# sound-detector.net
KiCad netlist of a schematic drawn in EAGLE
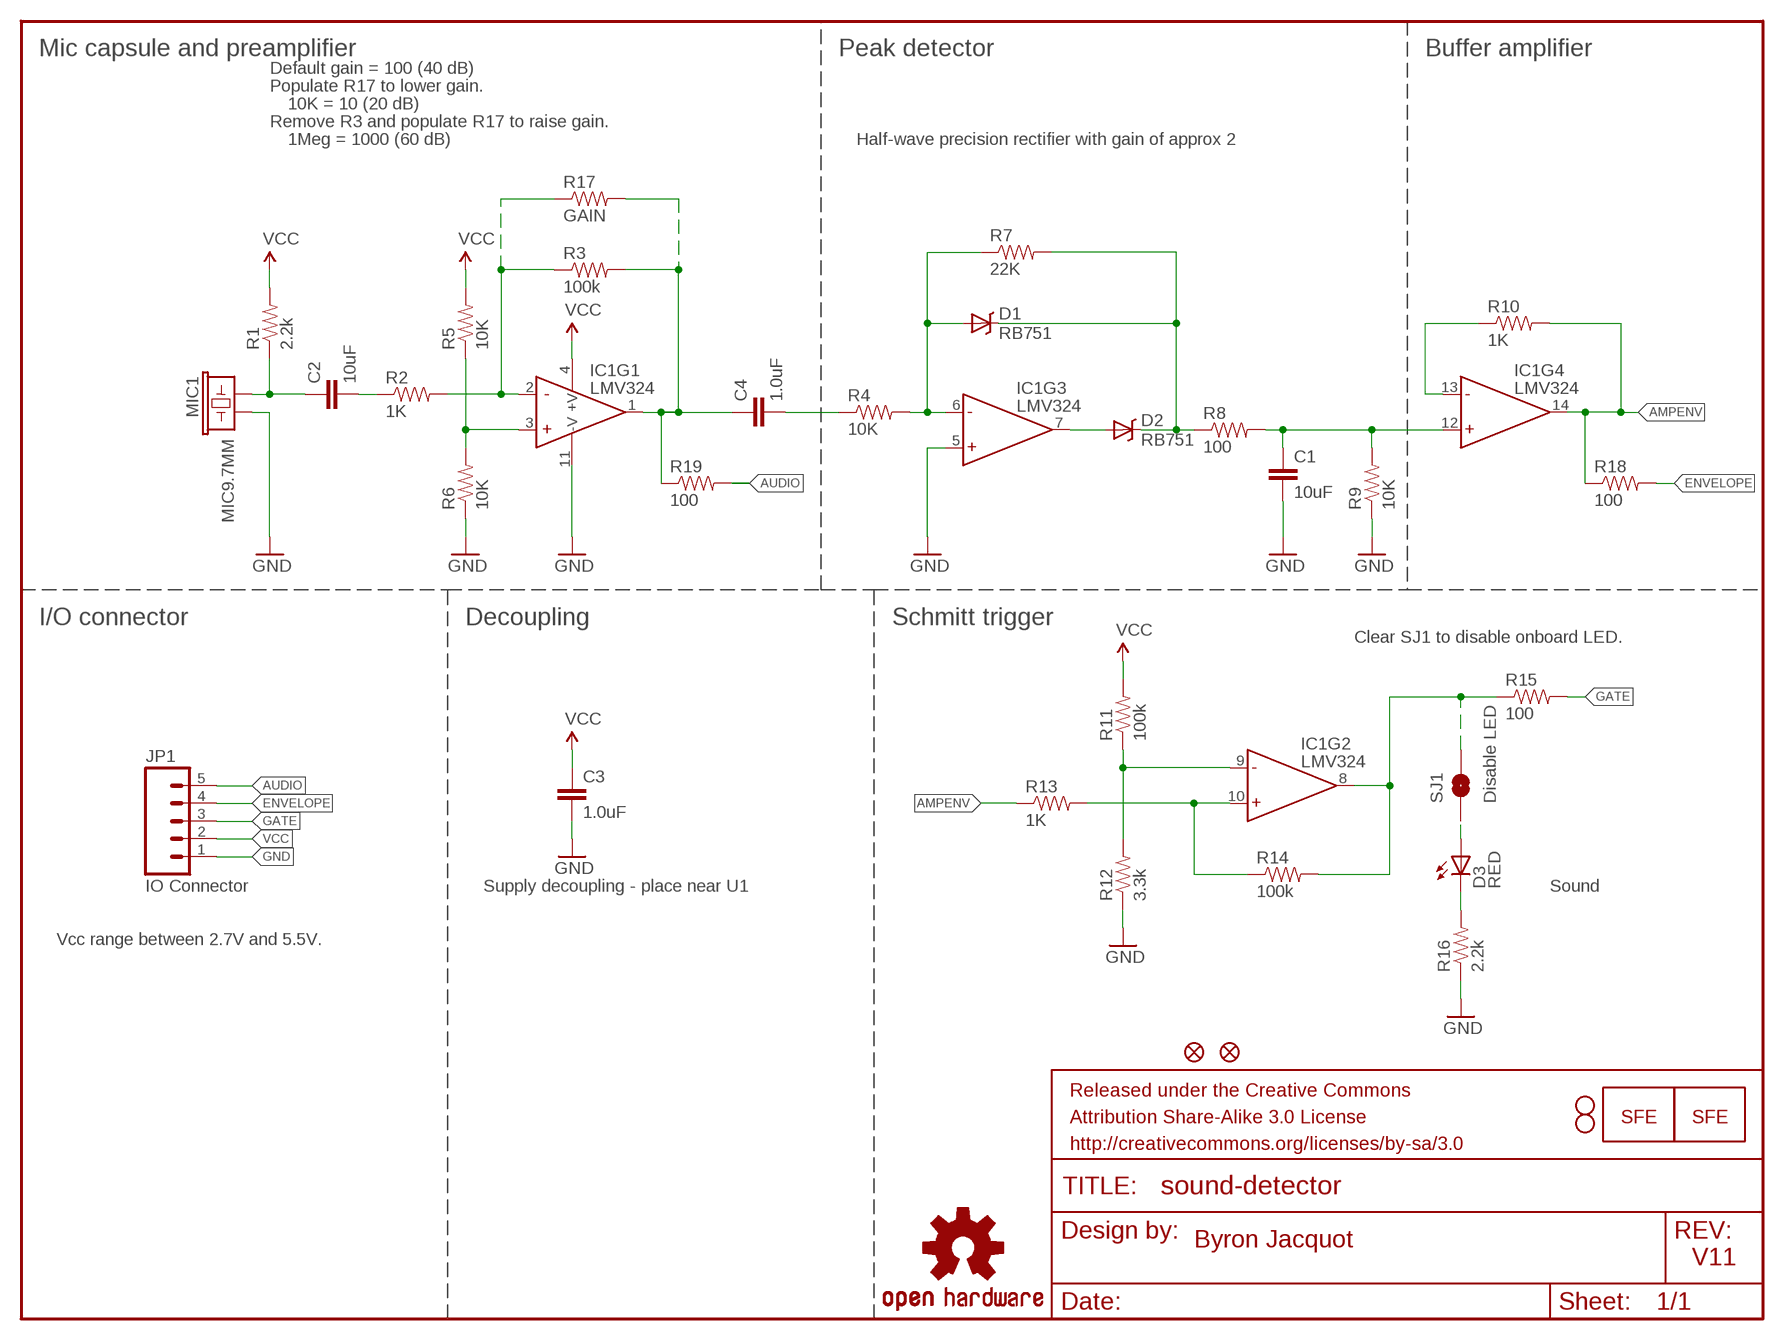
[diagram p0: schematic, sheet 1]

(export (version "E")
  (design (tool "Eeschema 10.0.6"))
  (components
    (comp (ref "C1")
      (value "10uF")
      (footprint "eagle-import:1206")
      (libsource (lib "eagle-import") (part "10UF-6.3V-20%(1206)"))
    )
    (comp (ref "C2")
      (value "10uF")
      (footprint "eagle-import:1206")
      (libsource (lib "eagle-import") (part "10UF-6.3V-20%(1206)"))
    )
    (comp (ref "C3")
      (value "1.0uF")
      (footprint "eagle-import:0603-CAP")
      (libsource (lib "eagle-import") (part "1.0UF-16V-10%(0603)"))
    )
    (comp (ref "C4")
      (value "1.0uF")
      (footprint "eagle-import:0603-CAP")
      (libsource (lib "eagle-import") (part "1.0UF-16V-10%(0603)"))
    )
    (comp (ref "D1")
      (value "RB751")
      (footprint "eagle-import:SOD-523")
      (libsource (lib "eagle-import") (part "RB751"))
    )
    (comp (ref "D2")
      (value "RB751")
      (footprint "eagle-import:SOD-523")
      (libsource (lib "eagle-import") (part "RB751"))
    )
    (comp (ref "D3")
      (value "RED")
      (footprint "eagle-import:LED-0603")
      (libsource (lib "eagle-import") (part "LED-RED0603"))
    )
    (comp (ref "FID3")
      (value "FIDUCIAL1X2")
      (footprint "eagle-import:FIDUCIAL-1X2")
      (libsource (lib "eagle-import") (part "FIDUCIAL1X2"))
    )
    (comp (ref "FID4")
      (value "FIDUCIAL1X2")
      (footprint "eagle-import:FIDUCIAL-1X2")
      (libsource (lib "eagle-import") (part "FIDUCIAL1X2"))
    )
    (comp (ref "FRAME1")
      (value "FRAME-LETTER")
      (footprint "eagle-import:CREATIVE_COMMONS")
      (libsource (lib "eagle-import") (part "FRAME-LETTER"))
    )
    (comp (ref "IC1")
      (value "LMV324")
      (footprint "eagle-import:SO014")
      (libsource (lib "eagle-import") (part "LMV324"))
    )
    (comp (ref "JP1")
      (value "IO Connector")
      (footprint "eagle-import:1X05")
      (libsource (lib "eagle-import") (part "M05PTH"))
    )
    (comp (ref "LOGO1")
      (value "OSHW-LOGOM")
      (footprint "eagle-import:OSHW-LOGO-M")
      (libsource (lib "eagle-import") (part "OSHW-LOGOM"))
    )
    (comp (ref "LOGO2")
      (value "LOGO-SFENW2")
      (footprint "eagle-import:SFE-NEW-WEB")
      (libsource (lib "eagle-import") (part "LOGO-SFENW2"))
    )
    (comp (ref "LOGO3")
      (value "LOGO-SFESK")
      (footprint "eagle-import:SFE-LOGO-FLAME")
      (libsource (lib "eagle-import") (part "LOGO-SFESK"))
    )
    (comp (ref "MIC1")
      (value "MIC9.7MM")
      (footprint "eagle-import:MIC-9.7MM")
      (libsource (lib "eagle-import") (part "MIC9.7MM"))
    )
    (comp (ref "R1")
      (value "2.2k")
      (footprint "eagle-import:0603-RES")
      (libsource (lib "eagle-import") (part "2.2KOHM1/10W1%(0603)"))
    )
    (comp (ref "R2")
      (value "1K")
      (footprint "eagle-import:0603-RES")
      (libsource (lib "eagle-import") (part "1KOHM1/10W1%(0603)"))
    )
    (comp (ref "R3")
      (value "100k")
      (footprint "eagle-import:0603-RES")
      (libsource (lib "eagle-import") (part "100KOHM1/10W1%(0603)"))
    )
    (comp (ref "R4")
      (value "10K")
      (footprint "eagle-import:0603-RES")
      (libsource (lib "eagle-import") (part "10KOHM1/10W1%(0603)0603"))
    )
    (comp (ref "R5")
      (value "10K")
      (footprint "eagle-import:0603-RES")
      (libsource (lib "eagle-import") (part "10KOHM1/10W1%(0603)0603"))
    )
    (comp (ref "R6")
      (value "10K")
      (footprint "eagle-import:0603-RES")
      (libsource (lib "eagle-import") (part "10KOHM1/10W1%(0603)0603"))
    )
    (comp (ref "R7")
      (value "22K")
      (footprint "eagle-import:0603-RES")
      (libsource (lib "eagle-import") (part "22KOHM1/10W1%(0603)"))
    )
    (comp (ref "R8")
      (value "100")
      (footprint "eagle-import:0603-RES")
      (libsource (lib "eagle-import") (part "100OHM1/10W1%(0603)"))
    )
    (comp (ref "R9")
      (value "10K")
      (footprint "eagle-import:0603-RES")
      (libsource (lib "eagle-import") (part "10KOHM1/10W1%(0603)0603"))
    )
    (comp (ref "R10")
      (value "1K")
      (footprint "eagle-import:0603-RES")
      (libsource (lib "eagle-import") (part "1KOHM1/10W1%(0603)"))
    )
    (comp (ref "R11")
      (value "100k")
      (footprint "eagle-import:0603-RES")
      (libsource (lib "eagle-import") (part "100KOHM1/10W1%(0603)"))
    )
    (comp (ref "R12")
      (value "3.3k")
      (footprint "eagle-import:0603-RES")
      (libsource (lib "eagle-import") (part "3.3KOHM1/10W1%(0603)"))
    )
    (comp (ref "R13")
      (value "1K")
      (footprint "eagle-import:0603-RES")
      (libsource (lib "eagle-import") (part "1KOHM1/10W1%(0603)"))
    )
    (comp (ref "R14")
      (value "100k")
      (footprint "eagle-import:0603-RES")
      (libsource (lib "eagle-import") (part "100KOHM1/10W1%(0603)"))
    )
    (comp (ref "R15")
      (value "100")
      (footprint "eagle-import:0603-RES")
      (libsource (lib "eagle-import") (part "100OHM1/10W1%(0603)"))
    )
    (comp (ref "R16")
      (value "2.2k")
      (footprint "eagle-import:0603-RES")
      (libsource (lib "eagle-import") (part "2.2KOHM1/10W1%(0603)"))
    )
    (comp (ref "R17")
      (value "GAIN")
      (footprint "eagle-import:AXIAL-0.1EZ")
      (libsource (lib "eagle-import") (part "RESISTORPTH-1/4W-VERT-KIT"))
    )
    (comp (ref "R18")
      (value "100")
      (footprint "eagle-import:0603-RES")
      (libsource (lib "eagle-import") (part "100OHM1/10W1%(0603)"))
    )
    (comp (ref "R19")
      (value "100")
      (footprint "eagle-import:0603-RES")
      (libsource (lib "eagle-import") (part "100OHM1/10W1%(0603)"))
    )
    (comp (ref "SJ1")
      (value "Disable LED")
      (footprint "eagle-import:SJ_2S")
      (libsource (lib "eagle-import") (part "SOLDERJUMPERNC"))
    )
    (comp (ref "STANDOFF1")
      (value "STAND-OFF")
      (footprint "eagle-import:STAND-OFF")
      (libsource (lib "eagle-import") (part "STAND-OFF"))
    )
    (comp (ref "STANDOFF2")
      (value "STAND-OFF")
      (footprint "eagle-import:STAND-OFF")
      (libsource (lib "eagle-import") (part "STAND-OFF"))
    )
  )
  (nets
    (net (code "1") (name "AMPENV") (class "Default")
      (node (ref "IC1") (pin "14") (pinfunction "OUT_14") (pintype "output"))
      (node (ref "R10") (pin "2") (pinfunction "2_2") (pintype "passive"))
      (node (ref "R13") (pin "1") (pinfunction "1_1") (pintype "passive"))
      (node (ref "R18") (pin "1") (pinfunction "1_1") (pintype "passive"))
    )
    (net (code "2") (name "AUDIO") (class "Default")
      (node (ref "JP1") (pin "5") (pinfunction "5_5") (pintype "passive"))
      (node (ref "R19") (pin "2") (pinfunction "2_2") (pintype "passive"))
    )
    (net (code "3") (name "ENVELOPE") (class "Default")
      (node (ref "JP1") (pin "4") (pinfunction "4_4") (pintype "passive"))
      (node (ref "R18") (pin "2") (pinfunction "2_2") (pintype "passive"))
    )
    (net (code "4") (name "GATE") (class "Default")
      (node (ref "JP1") (pin "3") (pinfunction "3_3") (pintype "passive"))
      (node (ref "R15") (pin "2") (pinfunction "2_2") (pintype "passive"))
    )
    (net (code "5") (name "GND") (class "Default")
      (node (ref "C1") (pin "2") (pinfunction "2_2") (pintype "passive"))
      (node (ref "C3") (pin "2") (pinfunction "2_2") (pintype "passive"))
      (node (ref "IC1") (pin "11") (pinfunction "-V_11") (pintype "power_in"))
      (node (ref "IC1") (pin "5") (pinfunction "+IN_5") (pintype "input"))
      (node (ref "JP1") (pin "1") (pinfunction "1_1") (pintype "passive"))
      (node (ref "MIC1") (pin "2") (pinfunction "2_2") (pintype "passive"))
      (node (ref "R12") (pin "1") (pinfunction "1_1") (pintype "passive"))
      (node (ref "R16") (pin "1") (pinfunction "1_1") (pintype "passive"))
      (node (ref "R6") (pin "1") (pinfunction "1_1") (pintype "passive"))
      (node (ref "R9") (pin "1") (pinfunction "1_1") (pintype "passive"))
    )
    (net (code "6") (name "Net-(C2-Pad1)") (class "Default")
      (node (ref "C2") (pin "1") (pinfunction "1_1") (pintype "passive"))
      (node (ref "MIC1") (pin "1") (pinfunction "1_1") (pintype "passive"))
      (node (ref "R1") (pin "1") (pinfunction "1_1") (pintype "passive"))
    )
    (net (code "7") (name "Net-(C2-Pad2)") (class "Default")
      (node (ref "C2") (pin "2") (pinfunction "2_2") (pintype "passive"))
      (node (ref "R2") (pin "1") (pinfunction "1_1") (pintype "passive"))
    )
    (net (code "8") (name "Net-(C4-Pad2)") (class "Default")
      (node (ref "C4") (pin "2") (pinfunction "2_2") (pintype "passive"))
      (node (ref "R4") (pin "1") (pinfunction "1_1") (pintype "passive"))
    )
    (net (code "9") (name "Net-(D1-PadC)") (class "Default")
      (node (ref "D1") (pin "C") (pinfunction "C_C") (pintype "passive"))
      (node (ref "D2") (pin "C") (pinfunction "C_C") (pintype "passive"))
      (node (ref "R7") (pin "2") (pinfunction "2_2") (pintype "passive"))
      (node (ref "R8") (pin "1") (pinfunction "1_1") (pintype "passive"))
    )
    (net (code "10") (name "Net-(D3-PadA)") (class "Default")
      (node (ref "D3") (pin "A") (pinfunction "A_A") (pintype "passive"))
      (node (ref "SJ1") (pin "1") (pinfunction "1_1") (pintype "passive"))
    )
    (net (code "11") (name "Net-(D3-PadC)") (class "Default")
      (node (ref "D3") (pin "C") (pinfunction "C_C") (pintype "passive"))
      (node (ref "R16") (pin "2") (pinfunction "2_2") (pintype "passive"))
    )
    (net (code "12") (name "Net-(IC1A-+IN)") (class "Default")
      (node (ref "IC1") (pin "3") (pinfunction "+IN_3") (pintype "input"))
      (node (ref "R5") (pin "1") (pinfunction "1_1") (pintype "passive"))
      (node (ref "R6") (pin "2") (pinfunction "2_2") (pintype "passive"))
    )
    (net (code "13") (name "Net-(IC1A--IN)") (class "Default")
      (node (ref "IC1") (pin "2") (pinfunction "-IN_2") (pintype "input"))
      (node (ref "R17") (pin "P$1") (pinfunction "1_P$1") (pintype "passive"))
      (node (ref "R2") (pin "2") (pinfunction "2_2") (pintype "passive"))
      (node (ref "R3") (pin "1") (pinfunction "1_1") (pintype "passive"))
    )
    (net (code "14") (name "Net-(IC1A-OUT)") (class "Default")
      (node (ref "C4") (pin "1") (pinfunction "1_1") (pintype "passive"))
      (node (ref "IC1") (pin "1") (pinfunction "OUT_1") (pintype "output"))
      (node (ref "R17") (pin "P$2") (pinfunction "2_P$2") (pintype "passive"))
      (node (ref "R19") (pin "1") (pinfunction "1_1") (pintype "passive"))
      (node (ref "R3") (pin "2") (pinfunction "2_2") (pintype "passive"))
    )
    (net (code "15") (name "Net-(IC1B-+IN)") (class "Default")
      (node (ref "IC1") (pin "10") (pinfunction "+IN_10") (pintype "input"))
      (node (ref "R13") (pin "2") (pinfunction "2_2") (pintype "passive"))
      (node (ref "R14") (pin "1") (pinfunction "1_1") (pintype "passive"))
    )
    (net (code "16") (name "Net-(IC1B--IN)") (class "Default")
      (node (ref "IC1") (pin "9") (pinfunction "-IN_9") (pintype "input"))
      (node (ref "R11") (pin "1") (pinfunction "1_1") (pintype "passive"))
      (node (ref "R12") (pin "2") (pinfunction "2_2") (pintype "passive"))
    )
    (net (code "17") (name "Net-(IC1B-OUT)") (class "Default")
      (node (ref "IC1") (pin "8") (pinfunction "OUT_8") (pintype "output"))
      (node (ref "R14") (pin "2") (pinfunction "2_2") (pintype "passive"))
      (node (ref "R15") (pin "1") (pinfunction "1_1") (pintype "passive"))
      (node (ref "SJ1") (pin "2") (pinfunction "2_2") (pintype "passive"))
    )
    (net (code "18") (name "Net-(IC1C--IN)") (class "Default")
      (node (ref "D1") (pin "A") (pinfunction "A_A") (pintype "passive"))
      (node (ref "IC1") (pin "6") (pinfunction "-IN_6") (pintype "input"))
      (node (ref "R4") (pin "2") (pinfunction "2_2") (pintype "passive"))
      (node (ref "R7") (pin "1") (pinfunction "1_1") (pintype "passive"))
    )
    (net (code "19") (name "Net-(IC1C-OUT)") (class "Default")
      (node (ref "D2") (pin "A") (pinfunction "A_A") (pintype "passive"))
      (node (ref "IC1") (pin "7") (pinfunction "OUT_7") (pintype "output"))
    )
    (net (code "20") (name "Net-(IC1D-+IN)") (class "Default")
      (node (ref "C1") (pin "1") (pinfunction "1_1") (pintype "passive"))
      (node (ref "IC1") (pin "12") (pinfunction "+IN_12") (pintype "input"))
      (node (ref "R8") (pin "2") (pinfunction "2_2") (pintype "passive"))
      (node (ref "R9") (pin "2") (pinfunction "2_2") (pintype "passive"))
    )
    (net (code "21") (name "Net-(IC1D--IN)") (class "Default")
      (node (ref "IC1") (pin "13") (pinfunction "-IN_13") (pintype "input"))
      (node (ref "R10") (pin "1") (pinfunction "1_1") (pintype "passive"))
    )
    (net (code "22") (name "VCC") (class "Default")
      (node (ref "C3") (pin "1") (pinfunction "1_1") (pintype "passive"))
      (node (ref "IC1") (pin "4") (pinfunction "+V_4") (pintype "power_in"))
      (node (ref "JP1") (pin "2") (pinfunction "2_2") (pintype "passive"))
      (node (ref "R1") (pin "2") (pinfunction "2_2") (pintype "passive"))
      (node (ref "R11") (pin "2") (pinfunction "2_2") (pintype "passive"))
      (node (ref "R5") (pin "2") (pinfunction "2_2") (pintype "passive"))
    )
  )
)
